# BNO055.net
KiCad netlist of a schematic drawn in Altium Designer
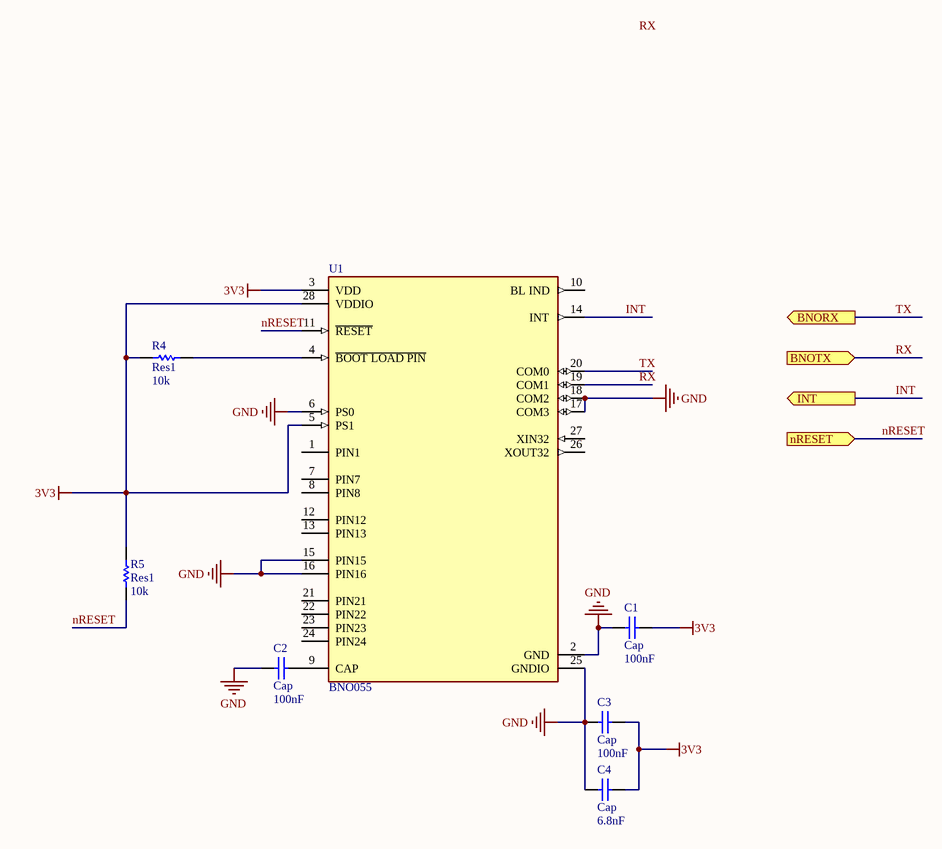
[diagram p0: BNO055.SchDoc]

(export (version "E")
  (design (tool "Eeschema 10.0.6"))
  (components
    (comp (ref "C1")
      (value "Cap")
      (footprint "0402-A")
      (description "Capacitor")
      (fields (field (name "ALTIUM_VALUE") "100nF") (field (name "PUBLISHER") "Altium Limited"))
      (libsource (lib "Miscellaneous Devices") (part "Cap"))
    )
    (comp (ref "C2")
      (value "Cap")
      (footprint "0402-A")
      (description "Capacitor")
      (fields (field (name "ALTIUM_VALUE") "100nF") (field (name "PUBLISHER") "Altium Limited"))
      (libsource (lib "Miscellaneous Devices") (part "Cap"))
    )
    (comp (ref "C3")
      (value "Cap")
      (footprint "0402-A")
      (description "Capacitor")
      (fields (field (name "ALTIUM_VALUE") "100nF") (field (name "PUBLISHER") "Altium Limited"))
      (libsource (lib "Miscellaneous Devices") (part "Cap"))
    )
    (comp (ref "C4")
      (value "Cap")
      (footprint "0402-A")
      (description "Capacitor")
      (fields (field (name "ALTIUM_VALUE") "6.8nF") (field (name "PUBLISHER") "Altium Limited"))
      (libsource (lib "Miscellaneous Devices") (part "Cap"))
    )
    (comp (ref "R4")
      (value "Res1")
      (footprint "0402-A")
      (description "Resistor")
      (fields (field (name "ALTIUM_VALUE") "10k") (field (name "PUBLISHER") "Altium Limited"))
      (libsource (lib "Miscellaneous Devices") (part "Res1"))
    )
    (comp (ref "R5")
      (value "Res1")
      (footprint "0402-A")
      (description "Resistor")
      (fields (field (name "ALTIUM_VALUE") "10k") (field (name "PUBLISHER") "Altium Limited"))
      (libsource (lib "Miscellaneous Devices") (part "Res1"))
    )
    (comp (ref "U1")
      (value "BNO055")
      (footprint "FP-BNO055-MFG")
      (description "IMU ACCEL/GYRO/MAG I2C 28LGA")
      (fields
        (field (name "OCTOPART") "https://octopart.com/bno055-bosch+sensortec-50309911")
        (field (name "VOLTAGE") "1.7~3.6V")
      )
      (libsource (lib "Altium Content Vault") (part "72d621e61db15910e840a84e68b4f76"))
    )
  )
  (nets
    (net (code "1") (name "/INT") (class "Default")
      (node (ref "U1") (pin "14") (pinfunction "INT_14") (pintype "output"))
    )
    (net (code "2") (name "/RX") (class "Default")
      (node (ref "U1") (pin "19") (pinfunction "COM1_19") (pintype "bidirectional"))
    )
    (net (code "3") (name "/TX") (class "Default")
      (node (ref "U1") (pin "20") (pinfunction "COM0_20") (pintype "bidirectional"))
    )
    (net (code "4") (name "/nRESET") (class "Default")
      (node (ref "R5") (pin "1") (pinfunction "1_1") (pintype "passive"))
      (node (ref "U1") (pin "11") (pinfunction "~{RESET}_11") (pintype "input"))
    )
    (net (code "5") (name "3V3") (class "Default")
      (node (ref "C1") (pin "2") (pinfunction "2_2") (pintype "passive"))
      (node (ref "C3") (pin "2") (pinfunction "2_2") (pintype "passive"))
      (node (ref "C4") (pin "2") (pinfunction "2_2") (pintype "passive"))
      (node (ref "R4") (pin "1") (pinfunction "1_1") (pintype "passive"))
      (node (ref "R5") (pin "2") (pinfunction "2_2") (pintype "passive"))
      (node (ref "U1") (pin "28") (pinfunction "VDDIO_28") (pintype "power_in"))
      (node (ref "U1") (pin "3") (pinfunction "VDD_3") (pintype "power_in"))
      (node (ref "U1") (pin "5") (pinfunction "PS1_5") (pintype "input"))
    )
    (net (code "6") (name "GND") (class "Default")
      (node (ref "C1") (pin "1") (pinfunction "1_1") (pintype "passive"))
      (node (ref "C2") (pin "1") (pinfunction "1_1") (pintype "passive"))
      (node (ref "C3") (pin "1") (pinfunction "1_1") (pintype "passive"))
      (node (ref "C4") (pin "1") (pinfunction "1_1") (pintype "passive"))
      (node (ref "U1") (pin "15") (pinfunction "PIN15_15") (pintype "power_in"))
      (node (ref "U1") (pin "16") (pinfunction "PIN16_16") (pintype "power_in"))
      (node (ref "U1") (pin "17") (pinfunction "COM3_17") (pintype "bidirectional"))
      (node (ref "U1") (pin "18") (pinfunction "COM2_18") (pintype "bidirectional"))
      (node (ref "U1") (pin "2") (pinfunction "GND_2") (pintype "power_in"))
      (node (ref "U1") (pin "25") (pinfunction "GNDIO_25") (pintype "power_in"))
      (node (ref "U1") (pin "6") (pinfunction "PS0_6") (pintype "input"))
    )
    (net (code "7") (name "Net-(U1-CAP)") (class "Default")
      (node (ref "C2") (pin "2") (pinfunction "2_2") (pintype "passive"))
      (node (ref "U1") (pin "9") (pinfunction "CAP_9") (pintype "passive"))
    )
    (net (code "8") (name "Net-(U1-~{BOOT_LOAD_PIN})") (class "Default")
      (node (ref "R4") (pin "2") (pinfunction "2_2") (pintype "passive"))
      (node (ref "U1") (pin "4") (pinfunction "~{BOOT_LOAD_PIN}_4") (pintype "input"))
    )
    (net (code "9") (name "unconnected-(U1-BL_IND-Pad10)") (class "Default")
      (node (ref "U1") (pin "10") (pinfunction "BL_IND_10") (pintype "output"))
    )
    (net (code "10") (name "unconnected-(U1-PIN1-Pad1)") (class "Default")
      (node (ref "U1") (pin "1") (pinfunction "PIN1_1") (pintype "passive"))
    )
    (net (code "11") (name "unconnected-(U1-PIN7-Pad7)") (class "Default")
      (node (ref "U1") (pin "7") (pinfunction "PIN7_7") (pintype "passive"))
    )
    (net (code "12") (name "unconnected-(U1-PIN8-Pad8)") (class "Default")
      (node (ref "U1") (pin "8") (pinfunction "PIN8_8") (pintype "passive"))
    )
    (net (code "13") (name "unconnected-(U1-PIN12-Pad12)") (class "Default")
      (node (ref "U1") (pin "12") (pinfunction "PIN12_12") (pintype "passive"))
    )
    (net (code "14") (name "unconnected-(U1-PIN13-Pad13)") (class "Default")
      (node (ref "U1") (pin "13") (pinfunction "PIN13_13") (pintype "passive"))
    )
    (net (code "15") (name "unconnected-(U1-PIN21-Pad21)") (class "Default")
      (node (ref "U1") (pin "21") (pinfunction "PIN21_21") (pintype "passive"))
    )
    (net (code "16") (name "unconnected-(U1-PIN22-Pad22)") (class "Default")
      (node (ref "U1") (pin "22") (pinfunction "PIN22_22") (pintype "passive"))
    )
    (net (code "17") (name "unconnected-(U1-PIN23-Pad23)") (class "Default")
      (node (ref "U1") (pin "23") (pinfunction "PIN23_23") (pintype "passive"))
    )
    (net (code "18") (name "unconnected-(U1-PIN24-Pad24)") (class "Default")
      (node (ref "U1") (pin "24") (pinfunction "PIN24_24") (pintype "passive"))
    )
    (net (code "19") (name "unconnected-(U1-XIN32-Pad27)") (class "Default")
      (node (ref "U1") (pin "27") (pinfunction "XIN32_27") (pintype "input"))
    )
    (net (code "20") (name "unconnected-(U1-XOUT32-Pad26)") (class "Default")
      (node (ref "U1") (pin "26") (pinfunction "XOUT32_26") (pintype "output"))
    )
  )
)
